# SkyLight.net
KiCad netlist of a schematic drawn in Altium Designer
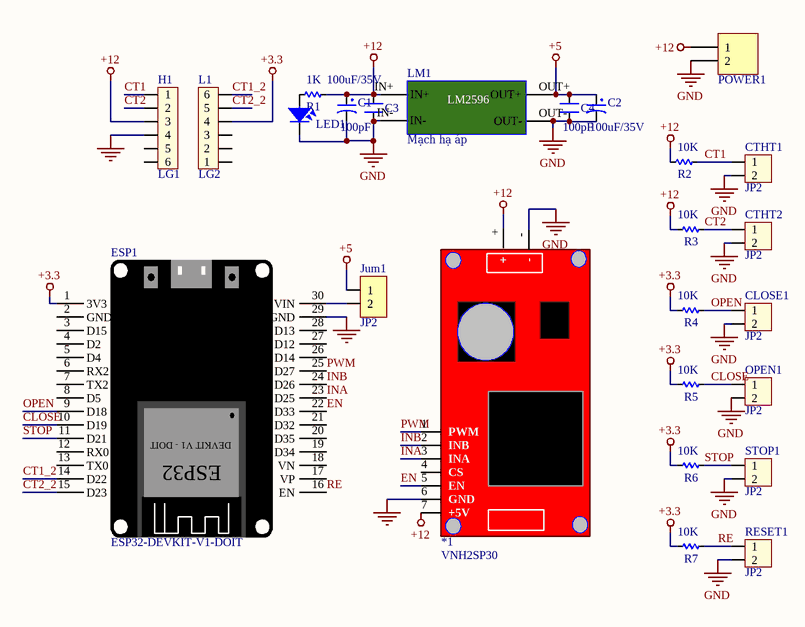
[diagram p0: SkyLight.SchDoc]

(export (version "E")
  (design (tool "Eeschema 10.0.6"))
  (components
    (comp (ref "*1")
      (value "VNH2SP30")
      (footprint "VNH2SP30")
      (libsource (lib "Nhuphung_Main") (part "VNH2SP30"))
    )
    (comp (ref "C1")
      (value "100uF/35V")
      (footprint "CP1.5/3.4")
      (description "Cap 100uF/35V - 470uF/16V")
      (libsource (lib "syhaunguyen") (part "CP3"))
    )
    (comp (ref "C2")
      (value "100uF/35V")
      (footprint "CP1.5/3.4")
      (description "Cap 100uF/35V - 470uF/16V")
      (libsource (lib "syhaunguyen") (part "CP3"))
    )
    (comp (ref "C3")
      (value "100pF")
      (footprint "CN1")
      (description "Cap np  1pF - 472pF")
      (libsource (lib "syhaunguyen") (part "CN1"))
    )
    (comp (ref "C4")
      (value "100pF")
      (footprint "CN1")
      (description "Cap np  1pF - 472pF")
      (libsource (lib "syhaunguyen") (part "CN1"))
    )
    (comp (ref "CLOSE1")
      (value "JP2")
      (footprint "CON2")
      (description "Connector 2")
      (libsource (lib "syhaunguyen") (part "Con2"))
    )
    (comp (ref "CTHT1")
      (value "JP2")
      (footprint "CON2")
      (description "Connector 2")
      (libsource (lib "syhaunguyen") (part "Con2"))
    )
    (comp (ref "CTHT2")
      (value "JP2")
      (footprint "CON2")
      (description "Connector 2")
      (libsource (lib "syhaunguyen") (part "Con2"))
    )
    (comp (ref "ESP1")
      (value "ESP32-DEVKIT-V1-DOIT")
      (footprint "ESP32-WROOM-32")
      (libsource (lib "Nhuphung_Main") (part "ESP32-DEVKIT-V1-DOIT"))
    )
    (comp (ref "H1")
      (value "LG1")
      (footprint "JP6")
      (description "JP6 PIN")
      (libsource (lib "") (part "JP6_1"))
    )
    (comp (ref "Jum1")
      (value "JP2")
      (footprint "JP2-CLOSED")
      (description "WR-PHD 2.54 mm Angled Socket Header")
      (fields
        (field (name "MANUFACTURER") "Würth Elektronik eiSos GmbH")
        (field (name "PARTNO") "613002143121")
        (field (name "CREATED BY") "Karrer Zheng")
      )
      (libsource (lib "LIBRARY (1)") (part "JP2"))
    )
    (comp (ref "L1")
      (value "LG2")
      (footprint "JP6")
      (description "JP6 PIN")
      (libsource (lib "syhaunguyen") (part "JP6"))
    )
    (comp (ref "LED1")
      (value "LED")
      (footprint "LED-5-RED")
      (description "LED Single colour Green and Red")
      (libsource (lib "LIBRARY (1)") (part "LED"))
    )
    (comp (ref "LM1")
      (value "Mạch hạ áp")
      (footprint "LM2596")
      (libsource (lib "Nhuphung_Main") (part "LM2596"))
    )
    (comp (ref "OPEN1")
      (value "JP2")
      (footprint "CON2")
      (description "Connector 2")
      (libsource (lib "syhaunguyen") (part "Con2"))
    )
    (comp (ref "POWER1")
      (value "Header 2_1")
      (footprint "HED2")
      (description "Header, 2-Pin")
      (fields (field (name "MANUFACTURER") "Generic Components"))
      (libsource (lib "syhaunguyen") (part "Header 2_1"))
    )
    (comp (ref "R1")
      (value "1K")
      (footprint "RES-1/4W-SMALL")
      (description "Res")
      (fields
        (field (name "MANUFACTURER") "Generic Components")
        (field (name "PUBLISHER") "Altium Hobart Technology Centre")
      )
      (libsource (lib "LIBRARY") (part "Res"))
    )
    (comp (ref "R2")
      (value "10K")
      (footprint "RES-1/4W-SMALL")
      (description "Res")
      (fields
        (field (name "MANUFACTURER") "Generic Components")
        (field (name "PUBLISHER") "Altium Hobart Technology Centre")
      )
      (libsource (lib "LIBRARY") (part "Res"))
    )
    (comp (ref "R3")
      (value "10K")
      (footprint "RES-1/4W-SMALL")
      (description "Res")
      (fields
        (field (name "MANUFACTURER") "Generic Components")
        (field (name "PUBLISHER") "Altium Hobart Technology Centre")
      )
      (libsource (lib "LIBRARY") (part "Res"))
    )
    (comp (ref "R4")
      (value "10K")
      (footprint "RES-1/4W-SMALL")
      (description "Res")
      (fields
        (field (name "MANUFACTURER") "Generic Components")
        (field (name "PUBLISHER") "Altium Hobart Technology Centre")
      )
      (libsource (lib "LIBRARY") (part "Res"))
    )
    (comp (ref "R5")
      (value "10K")
      (footprint "RES-1/4W-SMALL")
      (description "Res")
      (fields
        (field (name "MANUFACTURER") "Generic Components")
        (field (name "PUBLISHER") "Altium Hobart Technology Centre")
      )
      (libsource (lib "LIBRARY") (part "Res"))
    )
    (comp (ref "R6")
      (value "10K")
      (footprint "RES-1/4W-SMALL")
      (description "Res")
      (fields
        (field (name "MANUFACTURER") "Generic Components")
        (field (name "PUBLISHER") "Altium Hobart Technology Centre")
      )
      (libsource (lib "LIBRARY") (part "Res"))
    )
    (comp (ref "R7")
      (value "10K")
      (footprint "RES-1/4W-SMALL")
      (description "Res")
      (fields
        (field (name "MANUFACTURER") "Generic Components")
        (field (name "PUBLISHER") "Altium Hobart Technology Centre")
      )
      (libsource (lib "LIBRARY") (part "Res"))
    )
    (comp (ref "RESET1")
      (value "JP2")
      (footprint "CON2")
      (description "Connector 2")
      (libsource (lib "syhaunguyen") (part "Con2"))
    )
    (comp (ref "STOP1")
      (value "JP2")
      (footprint "CON2")
      (description "Connector 2")
      (libsource (lib "syhaunguyen") (part "Con2"))
    )
  )
  (nets
    (net (code "1") (name "+3.3") (class "Default")
      (node (ref "ESP1") (pin "1") (pinfunction "3V3_1") (pintype "passive"))
      (node (ref "L1") (pin "4") (pinfunction "4_4") (pintype "passive"))
      (node (ref "R4") (pin "1") (pinfunction "1_1") (pintype "passive"))
      (node (ref "R5") (pin "1") (pinfunction "1_1") (pintype "passive"))
      (node (ref "R6") (pin "1") (pinfunction "1_1") (pintype "passive"))
      (node (ref "R7") (pin "1") (pinfunction "1_1") (pintype "passive"))
    )
    (net (code "2") (name "+5") (class "Default")
      (node (ref "C2") (pin "1") (pinfunction "1_1") (pintype "passive"))
      (node (ref "C4") (pin "2") (pinfunction "2_2") (pintype "passive"))
      (node (ref "Jum1") (pin "1") (pinfunction "1_1") (pintype "passive"))
      (node (ref "LM1") (pin "OUT+") (pinfunction "OUT+_OUT+") (pintype "passive"))
    )
    (net (code "3") (name "+12") (class "Default")
      (node (ref "*1") (pin "+") (pinfunction "+_+") (pintype "passive"))
      (node (ref "*1") (pin "7") (pinfunction "+5V_7") (pintype "passive"))
      (node (ref "C1") (pin "1") (pinfunction "1_1") (pintype "passive"))
      (node (ref "C3") (pin "2") (pinfunction "2_2") (pintype "passive"))
      (node (ref "H1") (pin "3") (pinfunction "3_3") (pintype "passive"))
      (node (ref "LM1") (pin "IN+") (pinfunction "IN+_IN+") (pintype "passive"))
      (node (ref "POWER1") (pin "1") (pinfunction "1_1") (pintype "passive"))
      (node (ref "R1") (pin "2") (pinfunction "2_2") (pintype "passive"))
      (node (ref "R2") (pin "1") (pinfunction "1_1") (pintype "passive"))
      (node (ref "R3") (pin "1") (pinfunction "1_1") (pintype "passive"))
    )
    (net (code "4") (name "/CLOSE") (class "Default")
      (node (ref "ESP1") (pin "10") (pinfunction "D19_10") (pintype "passive"))
      (node (ref "OPEN1") (pin "1") (pinfunction "1_1") (pintype "passive"))
      (node (ref "R5") (pin "2") (pinfunction "2_2") (pintype "passive"))
    )
    (net (code "5") (name "/CT1") (class "Default")
      (node (ref "CTHT1") (pin "1") (pinfunction "1_1") (pintype "passive"))
      (node (ref "H1") (pin "1") (pinfunction "1_1") (pintype "passive"))
      (node (ref "R2") (pin "2") (pinfunction "2_2") (pintype "passive"))
    )
    (net (code "6") (name "/CT1_2") (class "Default")
      (node (ref "ESP1") (pin "14") (pinfunction "D22_14") (pintype "passive"))
      (node (ref "L1") (pin "6") (pinfunction "6_6") (pintype "passive"))
    )
    (net (code "7") (name "/CT2") (class "Default")
      (node (ref "CTHT2") (pin "1") (pinfunction "1_1") (pintype "passive"))
      (node (ref "H1") (pin "2") (pinfunction "2_2") (pintype "passive"))
      (node (ref "R3") (pin "2") (pinfunction "2_2") (pintype "passive"))
    )
    (net (code "8") (name "/CT2_2") (class "Default")
      (node (ref "ESP1") (pin "15") (pinfunction "D23_15") (pintype "passive"))
      (node (ref "L1") (pin "5") (pinfunction "5_5") (pintype "passive"))
    )
    (net (code "9") (name "/EN") (class "Default")
      (node (ref "*1") (pin "5") (pinfunction "EN_5") (pintype "passive"))
      (node (ref "ESP1") (pin "22") (pinfunction "D33_22") (pintype "passive"))
    )
    (net (code "10") (name "/INA") (class "Default")
      (node (ref "*1") (pin "3") (pinfunction "INA_3") (pintype "passive"))
      (node (ref "ESP1") (pin "23") (pinfunction "D25_23") (pintype "passive"))
    )
    (net (code "11") (name "/INB") (class "Default")
      (node (ref "*1") (pin "2") (pinfunction "INB_2") (pintype "passive"))
      (node (ref "ESP1") (pin "24") (pinfunction "D26_24") (pintype "passive"))
    )
    (net (code "12") (name "/OPEN") (class "Default")
      (node (ref "CLOSE1") (pin "1") (pinfunction "1_1") (pintype "passive"))
      (node (ref "ESP1") (pin "9") (pinfunction "D18_9") (pintype "passive"))
      (node (ref "R4") (pin "2") (pinfunction "2_2") (pintype "passive"))
    )
    (net (code "13") (name "/PWM") (class "Default")
      (node (ref "*1") (pin "1") (pinfunction "PWM_1") (pintype "passive"))
      (node (ref "ESP1") (pin "25") (pinfunction "D27_25") (pintype "passive"))
    )
    (net (code "14") (name "/RE") (class "Default")
      (node (ref "ESP1") (pin "16") (pinfunction "EN_16") (pintype "passive"))
      (node (ref "R7") (pin "2") (pinfunction "2_2") (pintype "passive"))
      (node (ref "RESET1") (pin "1") (pinfunction "1_1") (pintype "passive"))
    )
    (net (code "15") (name "/STOP") (class "Default")
      (node (ref "ESP1") (pin "11") (pinfunction "D21_11") (pintype "passive"))
      (node (ref "R6") (pin "2") (pinfunction "2_2") (pintype "passive"))
      (node (ref "STOP1") (pin "1") (pinfunction "1_1") (pintype "passive"))
    )
    (net (code "16") (name "GND") (class "Default")
      (node (ref "*1") (pin "-") (pinfunction "-_-") (pintype "passive"))
      (node (ref "*1") (pin "6") (pinfunction "GND_6") (pintype "passive"))
      (node (ref "C1") (pin "2") (pinfunction "2_2") (pintype "passive"))
      (node (ref "C2") (pin "2") (pinfunction "2_2") (pintype "passive"))
      (node (ref "C3") (pin "1") (pinfunction "1_1") (pintype "passive"))
      (node (ref "C4") (pin "1") (pinfunction "1_1") (pintype "passive"))
      (node (ref "CLOSE1") (pin "2") (pinfunction "2_2") (pintype "passive"))
      (node (ref "CTHT1") (pin "2") (pinfunction "2_2") (pintype "passive"))
      (node (ref "CTHT2") (pin "2") (pinfunction "2_2") (pintype "passive"))
      (node (ref "ESP1") (pin "29") (pinfunction "GND_29") (pintype "passive"))
      (node (ref "H1") (pin "4") (pinfunction "4_4") (pintype "passive"))
      (node (ref "LED1") (pin "2") (pinfunction "2_2") (pintype "passive"))
      (node (ref "LM1") (pin "IN-") (pinfunction "IN-_IN-") (pintype "passive"))
      (node (ref "LM1") (pin "OUT-") (pinfunction "OUT-_OUT-") (pintype "passive"))
      (node (ref "OPEN1") (pin "2") (pinfunction "2_2") (pintype "passive"))
      (node (ref "POWER1") (pin "2") (pinfunction "2_2") (pintype "passive"))
      (node (ref "RESET1") (pin "2") (pinfunction "2_2") (pintype "passive"))
      (node (ref "STOP1") (pin "2") (pinfunction "2_2") (pintype "passive"))
    )
    (net (code "17") (name "Net-(ESP1-VIN)") (class "Default")
      (node (ref "ESP1") (pin "30") (pinfunction "VIN_30") (pintype "passive"))
      (node (ref "Jum1") (pin "2") (pinfunction "2_2") (pintype "passive"))
    )
    (net (code "18") (name "Net-(LED1-Pad1)") (class "Default")
      (node (ref "LED1") (pin "1") (pinfunction "1_1") (pintype "passive"))
      (node (ref "R1") (pin "1") (pinfunction "1_1") (pintype "passive"))
    )
    (net (code "19") (name "unconnected-(*1-CS-Pad4)") (class "Default")
      (node (ref "*1") (pin "4") (pinfunction "CS_4") (pintype "passive"))
    )
    (net (code "20") (name "unconnected-(ESP1-D2-Pad4)") (class "Default")
      (node (ref "ESP1") (pin "4") (pinfunction "D2_4") (pintype "passive"))
    )
    (net (code "21") (name "unconnected-(ESP1-D4-Pad5)") (class "Default")
      (node (ref "ESP1") (pin "5") (pinfunction "D4_5") (pintype "passive"))
    )
    (net (code "22") (name "unconnected-(ESP1-D5-Pad8)") (class "Default")
      (node (ref "ESP1") (pin "8") (pinfunction "D5_8") (pintype "passive"))
    )
    (net (code "23") (name "unconnected-(ESP1-D12-Pad27)") (class "Default")
      (node (ref "ESP1") (pin "27") (pinfunction "D12_27") (pintype "passive"))
    )
    (net (code "24") (name "unconnected-(ESP1-D13-Pad28)") (class "Default")
      (node (ref "ESP1") (pin "28") (pinfunction "D13_28") (pintype "passive"))
    )
    (net (code "25") (name "unconnected-(ESP1-D14-Pad26)") (class "Default")
      (node (ref "ESP1") (pin "26") (pinfunction "D14_26") (pintype "passive"))
    )
    (net (code "26") (name "unconnected-(ESP1-D15-Pad3)") (class "Default")
      (node (ref "ESP1") (pin "3") (pinfunction "D15_3") (pintype "passive"))
    )
    (net (code "27") (name "unconnected-(ESP1-D32-Pad21)") (class "Default")
      (node (ref "ESP1") (pin "21") (pinfunction "D32_21") (pintype "passive"))
    )
    (net (code "28") (name "unconnected-(ESP1-D34-Pad19)") (class "Default")
      (node (ref "ESP1") (pin "19") (pinfunction "D34_19") (pintype "passive"))
    )
    (net (code "29") (name "unconnected-(ESP1-D35-Pad20)") (class "Default")
      (node (ref "ESP1") (pin "20") (pinfunction "D35_20") (pintype "passive"))
    )
    (net (code "30") (name "unconnected-(ESP1-GND-Pad2)") (class "Default")
      (node (ref "ESP1") (pin "2") (pinfunction "GND_2") (pintype "passive"))
    )
    (net (code "31") (name "unconnected-(ESP1-RX0-Pad12)") (class "Default")
      (node (ref "ESP1") (pin "12") (pinfunction "RX0_12") (pintype "passive"))
    )
    (net (code "32") (name "unconnected-(ESP1-RX2-Pad6)") (class "Default")
      (node (ref "ESP1") (pin "6") (pinfunction "RX2_6") (pintype "passive"))
    )
    (net (code "33") (name "unconnected-(ESP1-TX0-Pad13)") (class "Default")
      (node (ref "ESP1") (pin "13") (pinfunction "TX0_13") (pintype "passive"))
    )
    (net (code "34") (name "unconnected-(ESP1-TX2-Pad7)") (class "Default")
      (node (ref "ESP1") (pin "7") (pinfunction "TX2_7") (pintype "passive"))
    )
    (net (code "35") (name "unconnected-(ESP1-VN-Pad18)") (class "Default")
      (node (ref "ESP1") (pin "18") (pinfunction "VN_18") (pintype "passive"))
    )
    (net (code "36") (name "unconnected-(ESP1-VP-Pad17)") (class "Default")
      (node (ref "ESP1") (pin "17") (pinfunction "VP_17") (pintype "passive"))
    )
    (net (code "37") (name "unconnected-(H1-Pad5)") (class "Default")
      (node (ref "H1") (pin "5") (pinfunction "5_5") (pintype "passive"))
    )
    (net (code "38") (name "unconnected-(H1-Pad6)") (class "Default")
      (node (ref "H1") (pin "6") (pinfunction "6_6") (pintype "passive"))
    )
    (net (code "39") (name "unconnected-(L1-Pad1)") (class "Default")
      (node (ref "L1") (pin "1") (pinfunction "1_1") (pintype "passive"))
    )
    (net (code "40") (name "unconnected-(L1-Pad2)") (class "Default")
      (node (ref "L1") (pin "2") (pinfunction "2_2") (pintype "passive"))
    )
    (net (code "41") (name "unconnected-(L1-Pad3)") (class "Default")
      (node (ref "L1") (pin "3") (pinfunction "3_3") (pintype "passive"))
    )
  )
)
